# Micphone.net
KiCad netlist of a schematic drawn in Altium Designer
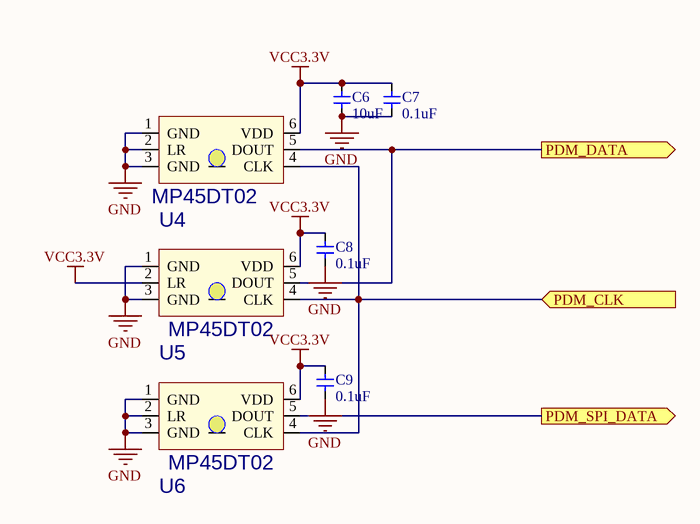
[diagram p0: Micphone.SchDoc]

(export (version "E")
  (design (tool "Eeschema 10.0.6"))
  (components
    (comp (ref "C6")
      (value "10uF")
      (footprint "PCB_PassiveCap:CAP_0603")
      (description "Capacitor")
      (fields (field (name "Comment") "Cap_0603"))
      (libsource (lib "SCH_Passive") (part "Cap_0603"))
    )
    (comp (ref "C7")
      (value "0.1uF")
      (footprint "PCB_PassiveCap:CAP_0603")
      (description "Capacitor")
      (fields (field (name "Comment") "Cap_0603"))
      (libsource (lib "SCH_Passive") (part "Cap_0603"))
    )
    (comp (ref "C8")
      (value "0.1uF")
      (footprint "PCB_PassiveCap:CAP_0603")
      (description "Capacitor")
      (fields (field (name "Comment") "Cap_0603"))
      (libsource (lib "SCH_Passive") (part "Cap_0603"))
    )
    (comp (ref "C9")
      (value "0.1uF")
      (footprint "PCB_PassiveCap:CAP_0603")
      (description "Capacitor")
      (fields (field (name "Comment") "Cap_0603"))
      (libsource (lib "SCH_Passive") (part "Cap_0603"))
    )
    (comp (ref "U4")
      (value "MP45DT02")
      (footprint "ST_HLGA6")
      (description "Mic Omni-Directional -26dB 3.6V Rectangular Solder Pad")
      (fields (field (name "MF") "STMicroelectronics"))
      (libsource (lib "SCH_IntegratedCircuit") (part "MP45DT02"))
    )
    (comp (ref "U5")
      (value "MP45DT02")
      (footprint "ST_HLGA6")
      (description "Mic Omni-Directional -26dB 3.6V Rectangular Solder Pad")
      (fields (field (name "MF") "STMicroelectronics"))
      (libsource (lib "SCH_IntegratedCircuit") (part "MP45DT02"))
    )
    (comp (ref "U6")
      (value "MP45DT02")
      (footprint "ST_HLGA6")
      (description "Mic Omni-Directional -26dB 3.6V Rectangular Solder Pad")
      (fields (field (name "MF") "STMicroelectronics"))
      (libsource (lib "SCH_IntegratedCircuit") (part "MP45DT02"))
    )
  )
  (nets
    (net (code "1") (name "/PDM_CLK") (class "Default")
      (node (ref "U4") (pin "4") (pinfunction "CLK_4") (pintype "passive"))
      (node (ref "U5") (pin "4") (pinfunction "CLK_4") (pintype "passive"))
      (node (ref "U6") (pin "4") (pinfunction "CLK_4") (pintype "passive"))
    )
    (net (code "2") (name "/PDM_DATA") (class "Default")
      (node (ref "U4") (pin "5") (pinfunction "DOUT_5") (pintype "passive"))
      (node (ref "U5") (pin "5") (pinfunction "DOUT_5") (pintype "passive"))
    )
    (net (code "3") (name "/PDM_SPI_DATA") (class "Default")
      (node (ref "U6") (pin "5") (pinfunction "DOUT_5") (pintype "passive"))
    )
    (net (code "4") (name "GND") (class "Default")
      (node (ref "C6") (pin "1") (pinfunction "1_1") (pintype "passive"))
      (node (ref "C7") (pin "1") (pinfunction "1_1") (pintype "passive"))
      (node (ref "C8") (pin "1") (pinfunction "1_1") (pintype "passive"))
      (node (ref "C9") (pin "1") (pinfunction "1_1") (pintype "passive"))
      (node (ref "U4") (pin "1") (pinfunction "GND_1") (pintype "passive"))
      (node (ref "U4") (pin "2") (pinfunction "LR_2") (pintype "passive"))
      (node (ref "U4") (pin "3") (pinfunction "GND_3") (pintype "passive"))
      (node (ref "U5") (pin "1") (pinfunction "GND_1") (pintype "passive"))
      (node (ref "U5") (pin "3") (pinfunction "GND_3") (pintype "passive"))
      (node (ref "U6") (pin "1") (pinfunction "GND_1") (pintype "passive"))
      (node (ref "U6") (pin "2") (pinfunction "LR_2") (pintype "passive"))
      (node (ref "U6") (pin "3") (pinfunction "GND_3") (pintype "passive"))
    )
    (net (code "5") (name "VCC3.3V") (class "Default")
      (node (ref "C6") (pin "2") (pinfunction "2_2") (pintype "passive"))
      (node (ref "C7") (pin "2") (pinfunction "2_2") (pintype "passive"))
      (node (ref "C8") (pin "2") (pinfunction "2_2") (pintype "passive"))
      (node (ref "C9") (pin "2") (pinfunction "2_2") (pintype "passive"))
      (node (ref "U4") (pin "6") (pinfunction "VDD_6") (pintype "passive"))
      (node (ref "U5") (pin "2") (pinfunction "LR_2") (pintype "passive"))
      (node (ref "U5") (pin "6") (pinfunction "VDD_6") (pintype "passive"))
      (node (ref "U6") (pin "6") (pinfunction "VDD_6") (pintype "passive"))
    )
  )
)
